# PCB_temp.net
KiCad netlist of a schematic drawn in Altium Designer
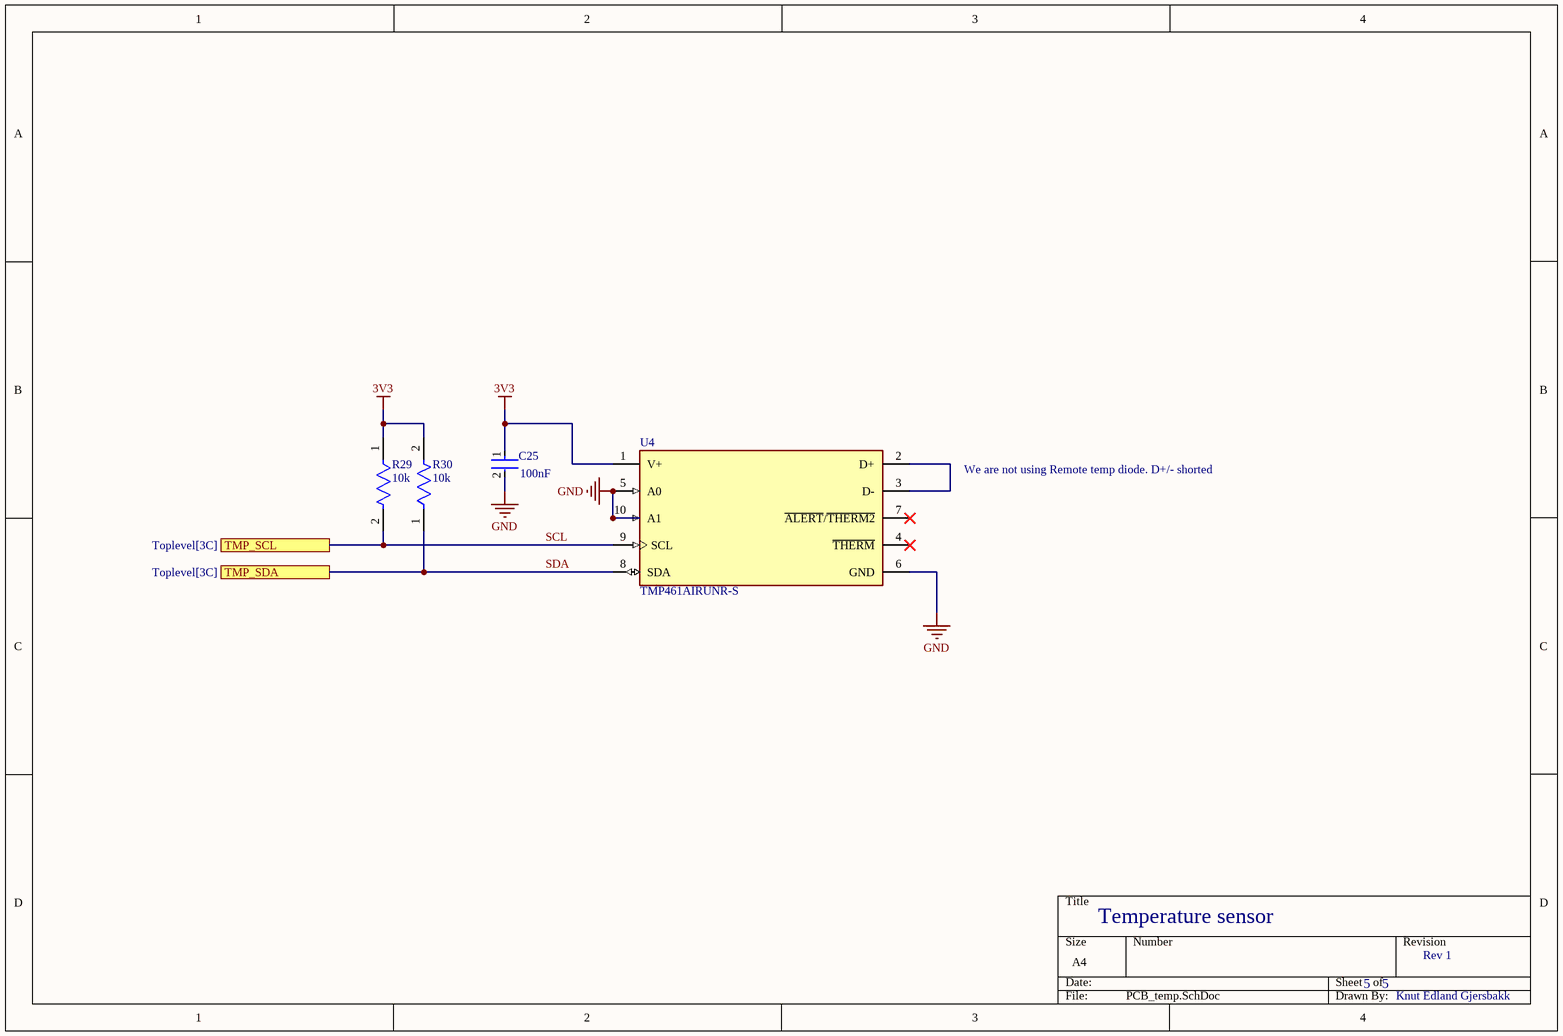
[diagram p0: PCB_temp.SchDoc]

(export (version "E")
  (design (tool "Eeschema 10.0.6"))
  (components
    (comp (ref "C25")
      (value "100nF")
      (footprint "FP-CL10-IPC_A")
      (description "Cap Ceramic 100nF 16V X7R ±10% Pad SMD 0603 +125°C T/R")
      (fields (field (name "TOLERANCE") "10%"))
      (libsource (lib "Altium Content Vault") (part "b4654b650e69147ec39a6b967a45e02"))
    )
    (comp (ref "R29")
      (value "10k")
      (footprint "FP-RT0603-IPC_C")
      (description "RES SMD 10K OHM 1% 1/10W 0603\r\nRT0603FRE0710KL")
      (fields
        (field (name "MANUFACTURER") "Yageo")
        (field (name "OCTOPART") "https://octopart.com/rt0603fre0710kl-yageo-40009243")
      )
      (libsource (lib "Altium Content Vault") (part "1029c3af85768c4190bb7ad29bc67b5"))
    )
    (comp (ref "R30")
      (value "10k")
      (footprint "FP-RT0603-IPC_C")
      (description "RES SMD 10K OHM 1% 1/10W 0603\r\nRT0603FRE0710KL")
      (fields
        (field (name "MANUFACTURER") "Yageo")
        (field (name "OCTOPART") "https://octopart.com/rt0603fre0710kl-yageo-40009243")
      )
      (libsource (lib "Altium Content Vault") (part "1029c3af85768c4190bb7ad29bc67b5"))
    )
    (comp (ref "U4")
      (value "TMP461AIRUNR-S")
      (footprint "FP-RUN0010A-MFG")
      (description "TMP461AIRUNR-S Temperature Sensor Digital, Local/Remote -40°C ~ 125°C 11 b 10-WQFN (2x2)")
      (libsource (lib "Altium Content Vault") (part "1dbd92a773e9bf4290f1d0262c0b827"))
    )
  )
  (nets
    (net (code "1") (name "/SCL") (class "Default")
      (node (ref "R29") (pin "2") (pinfunction "2_2") (pintype "passive"))
      (node (ref "U4") (pin "9") (pinfunction "SCL_9") (pintype "input"))
    )
    (net (code "2") (name "/SDA") (class "Default")
      (node (ref "R30") (pin "1") (pinfunction "1_1") (pintype "passive"))
      (node (ref "U4") (pin "8") (pinfunction "SDA_8") (pintype "bidirectional"))
    )
    (net (code "3") (name "3V3") (class "Default")
      (node (ref "C25") (pin "1") (pinfunction "1_1") (pintype "passive"))
      (node (ref "R29") (pin "1") (pinfunction "1_1") (pintype "passive"))
      (node (ref "R30") (pin "2") (pinfunction "2_2") (pintype "passive"))
      (node (ref "U4") (pin "1") (pinfunction "V+_1") (pintype "power_in"))
    )
    (net (code "4") (name "GND") (class "Default")
      (node (ref "C25") (pin "2") (pinfunction "2_2") (pintype "passive"))
      (node (ref "U4") (pin "10") (pinfunction "A1_10") (pintype "input"))
      (node (ref "U4") (pin "5") (pinfunction "A0_5") (pintype "input"))
      (node (ref "U4") (pin "6") (pinfunction "GND_6") (pintype "power_in"))
    )
    (net (code "5") (name "Net-(U4-D+)") (class "Default")
      (node (ref "U4") (pin "2") (pinfunction "D+_2") (pintype "passive"))
      (node (ref "U4") (pin "3") (pinfunction "D-_3") (pintype "passive"))
    )
    (net (code "6") (name "unconnected-(U4-~{ALERT}{slash}~{THERM2}-Pad7)") (class "Default")
      (node (ref "U4") (pin "7") (pinfunction "~{ALERT}/~{THERM2}_7") (pintype "open_collector+no_connect"))
    )
    (net (code "7") (name "unconnected-(U4-~{THERM}-Pad4)") (class "Default")
      (node (ref "U4") (pin "4") (pinfunction "~{THERM}_4") (pintype "open_collector+no_connect"))
    )
  )
)
